# Controller.net
KiCad netlist of a schematic drawn in EAGLE
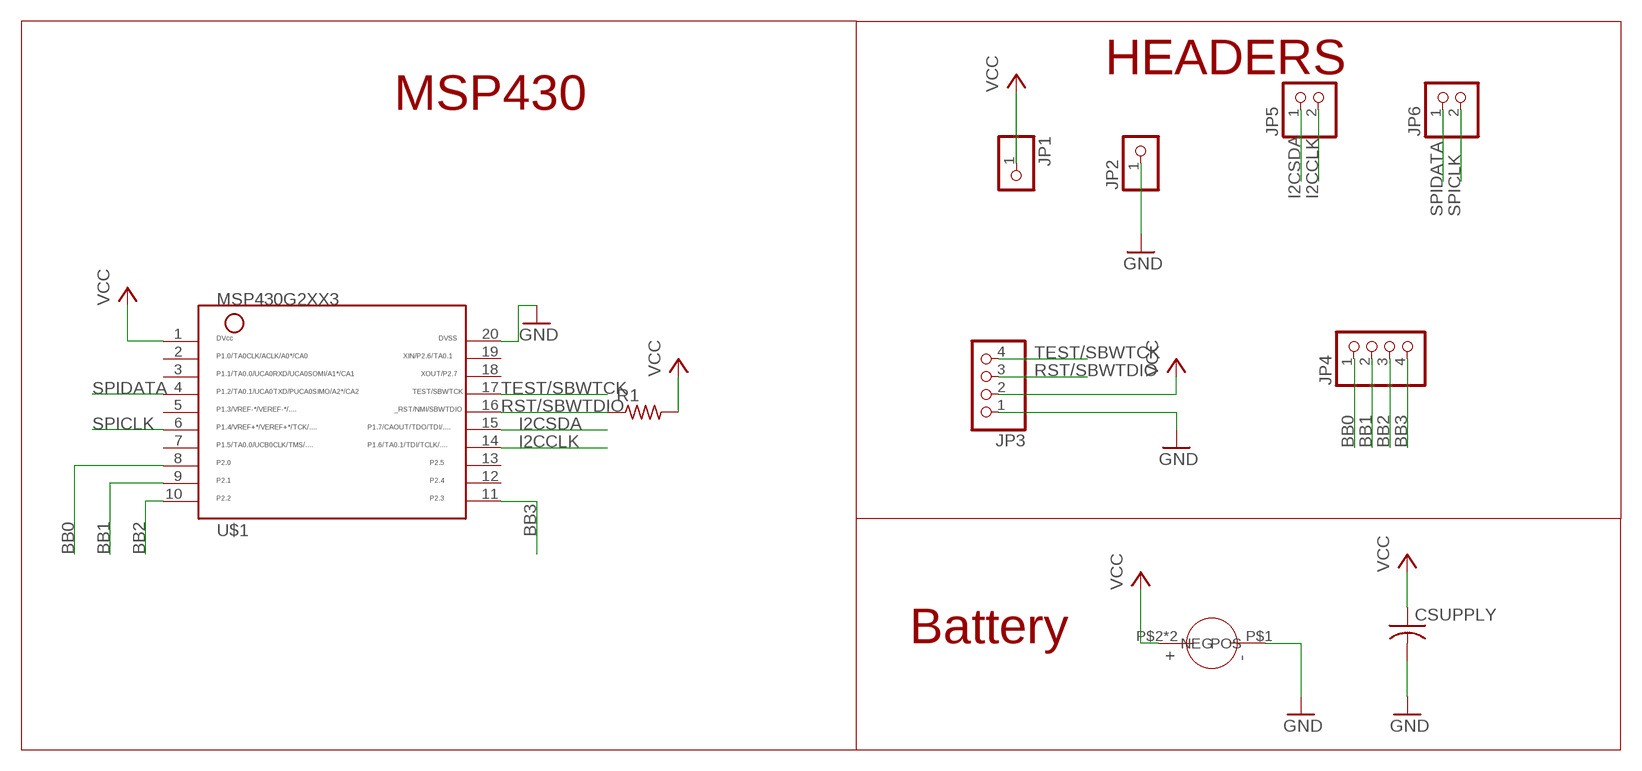
[diagram p0: schematic, sheet 1]

(export (version "E")
  (design (tool "Eeschema 10.0.6"))
  (components
    (comp (ref "CSUPPLY")
      (value "C-USC1206")
      (footprint "eagle-import:C1206")
      (libsource (lib "eagle-import") (part "C-USC1206"))
    )
    (comp (ref "JP1")
      (value "PINHD-1X1")
      (footprint "eagle-import:1X01")
      (libsource (lib "eagle-import") (part "PINHD-1X1"))
    )
    (comp (ref "JP2")
      (value "PINHD-1X1")
      (footprint "eagle-import:1X01")
      (libsource (lib "eagle-import") (part "PINHD-1X1"))
    )
    (comp (ref "JP3")
      (value "PINHD-1X4")
      (footprint "eagle-import:1X04")
      (libsource (lib "eagle-import") (part "PINHD-1X4"))
    )
    (comp (ref "JP4")
      (value "PINHD-1X4")
      (footprint "eagle-import:1X04")
      (libsource (lib "eagle-import") (part "PINHD-1X4"))
    )
    (comp (ref "JP5")
      (value "PINHD-1X2")
      (footprint "eagle-import:1X02")
      (libsource (lib "eagle-import") (part "PINHD-1X2"))
    )
    (comp (ref "JP6")
      (value "PINHD-1X2")
      (footprint "eagle-import:1X02")
      (libsource (lib "eagle-import") (part "PINHD-1X2"))
    )
    (comp (ref "R1")
      (value "R-US_R1206")
      (footprint "eagle-import:R1206")
      (libsource (lib "eagle-import") (part "R-US_R1206"))
    )
    (comp (ref "U$1")
      (value "MSP430G2XX3TSSOP")
      (footprint "eagle-import:PW20")
      (libsource (lib "eagle-import") (part "MSP430G2XX3TSSOP"))
    )
    (comp (ref "U$2")
      (value "3002BATTERY")
      (footprint "eagle-import:3002BATTERY")
      (libsource (lib "eagle-import") (part "3002BATTERY"))
    )
  )
  (nets
    (net (code "1") (name "/BB0") (class "Default")
      (node (ref "JP4") (pin "1") (pinfunction "1_1") (pintype "passive"))
      (node (ref "U$1") (pin "8") (pinfunction "8_8") (pintype "bidirectional"))
    )
    (net (code "2") (name "/BB1") (class "Default")
      (node (ref "JP4") (pin "2") (pinfunction "2_2") (pintype "passive"))
      (node (ref "U$1") (pin "9") (pinfunction "9_9") (pintype "bidirectional"))
    )
    (net (code "3") (name "/BB2") (class "Default")
      (node (ref "JP4") (pin "3") (pinfunction "3_3") (pintype "passive"))
      (node (ref "U$1") (pin "10") (pinfunction "10_10") (pintype "bidirectional"))
    )
    (net (code "4") (name "/BB3") (class "Default")
      (node (ref "JP4") (pin "4") (pinfunction "4_4") (pintype "passive"))
      (node (ref "U$1") (pin "11") (pinfunction "11_11") (pintype "bidirectional"))
    )
    (net (code "5") (name "/I2CCLK") (class "Default")
      (node (ref "JP5") (pin "2") (pinfunction "2_2") (pintype "passive"))
      (node (ref "U$1") (pin "14") (pinfunction "14_14") (pintype "bidirectional"))
    )
    (net (code "6") (name "/I2CSDA") (class "Default")
      (node (ref "JP5") (pin "1") (pinfunction "1_1") (pintype "passive"))
      (node (ref "U$1") (pin "15") (pinfunction "15_15") (pintype "bidirectional"))
    )
    (net (code "7") (name "/RST{slash}SBWTDIO") (class "Default")
      (node (ref "JP3") (pin "3") (pinfunction "3_3") (pintype "passive"))
      (node (ref "R1") (pin "1") (pinfunction "1_1") (pintype "passive"))
      (node (ref "U$1") (pin "16") (pinfunction "16_16") (pintype "bidirectional"))
    )
    (net (code "8") (name "/SPICLK") (class "Default")
      (node (ref "JP6") (pin "2") (pinfunction "2_2") (pintype "passive"))
      (node (ref "U$1") (pin "6") (pinfunction "6_6") (pintype "bidirectional"))
    )
    (net (code "9") (name "/SPIDATA") (class "Default")
      (node (ref "JP6") (pin "1") (pinfunction "1_1") (pintype "passive"))
      (node (ref "U$1") (pin "4") (pinfunction "4_4") (pintype "bidirectional"))
    )
    (net (code "10") (name "/TEST{slash}SBWTCK") (class "Default")
      (node (ref "JP3") (pin "4") (pinfunction "4_4") (pintype "passive"))
      (node (ref "U$1") (pin "17") (pinfunction "17_17") (pintype "bidirectional"))
    )
    (net (code "11") (name "GND") (class "Default")
      (node (ref "CSUPPLY") (pin "2") (pinfunction "2_2") (pintype "passive"))
      (node (ref "JP2") (pin "1") (pinfunction "1_1") (pintype "passive"))
      (node (ref "JP3") (pin "1") (pinfunction "1_1") (pintype "passive"))
      (node (ref "U$1") (pin "20") (pinfunction "20_20") (pintype "bidirectional"))
      (node (ref "U$2") (pin "P$1") (pinfunction "NEG_P$1") (pintype "bidirectional"))
    )
    (net (code "12") (name "VCC") (class "Default")
      (node (ref "CSUPPLY") (pin "1") (pinfunction "1_1") (pintype "passive"))
      (node (ref "JP1") (pin "1") (pinfunction "1_1") (pintype "passive"))
      (node (ref "JP3") (pin "2") (pinfunction "2_2") (pintype "passive"))
      (node (ref "R1") (pin "2") (pinfunction "2_2") (pintype "passive"))
      (node (ref "U$1") (pin "1") (pinfunction "1_1") (pintype "bidirectional"))
      (node (ref "U$2") (pin "P$2") (pinfunction "POS_P$2") (pintype "bidirectional"))
      (node (ref "U$2") (pin "P$3") (pinfunction "POS_P$3") (pintype "bidirectional"))
    )
    (net (code "13") (name "unconnected-(U$1-Pad2)") (class "Default")
      (node (ref "U$1") (pin "2") (pinfunction "2_2") (pintype "bidirectional"))
    )
    (net (code "14") (name "unconnected-(U$1-Pad3)") (class "Default")
      (node (ref "U$1") (pin "3") (pinfunction "3_3") (pintype "bidirectional"))
    )
    (net (code "15") (name "unconnected-(U$1-Pad5)") (class "Default")
      (node (ref "U$1") (pin "5") (pinfunction "5_5") (pintype "bidirectional"))
    )
    (net (code "16") (name "unconnected-(U$1-Pad7)") (class "Default")
      (node (ref "U$1") (pin "7") (pinfunction "7_7") (pintype "bidirectional"))
    )
    (net (code "17") (name "unconnected-(U$1-Pad12)") (class "Default")
      (node (ref "U$1") (pin "12") (pinfunction "12_12") (pintype "bidirectional"))
    )
    (net (code "18") (name "unconnected-(U$1-Pad13)") (class "Default")
      (node (ref "U$1") (pin "13") (pinfunction "13_13") (pintype "bidirectional"))
    )
    (net (code "19") (name "unconnected-(U$1-Pad18)") (class "Default")
      (node (ref "U$1") (pin "18") (pinfunction "18_18") (pintype "bidirectional"))
    )
    (net (code "20") (name "unconnected-(U$1-Pad19)") (class "Default")
      (node (ref "U$1") (pin "19") (pinfunction "19_19") (pintype "bidirectional"))
    )
  )
)
